# microXusb401_r15.net
KiCad netlist of a schematic drawn in EAGLE
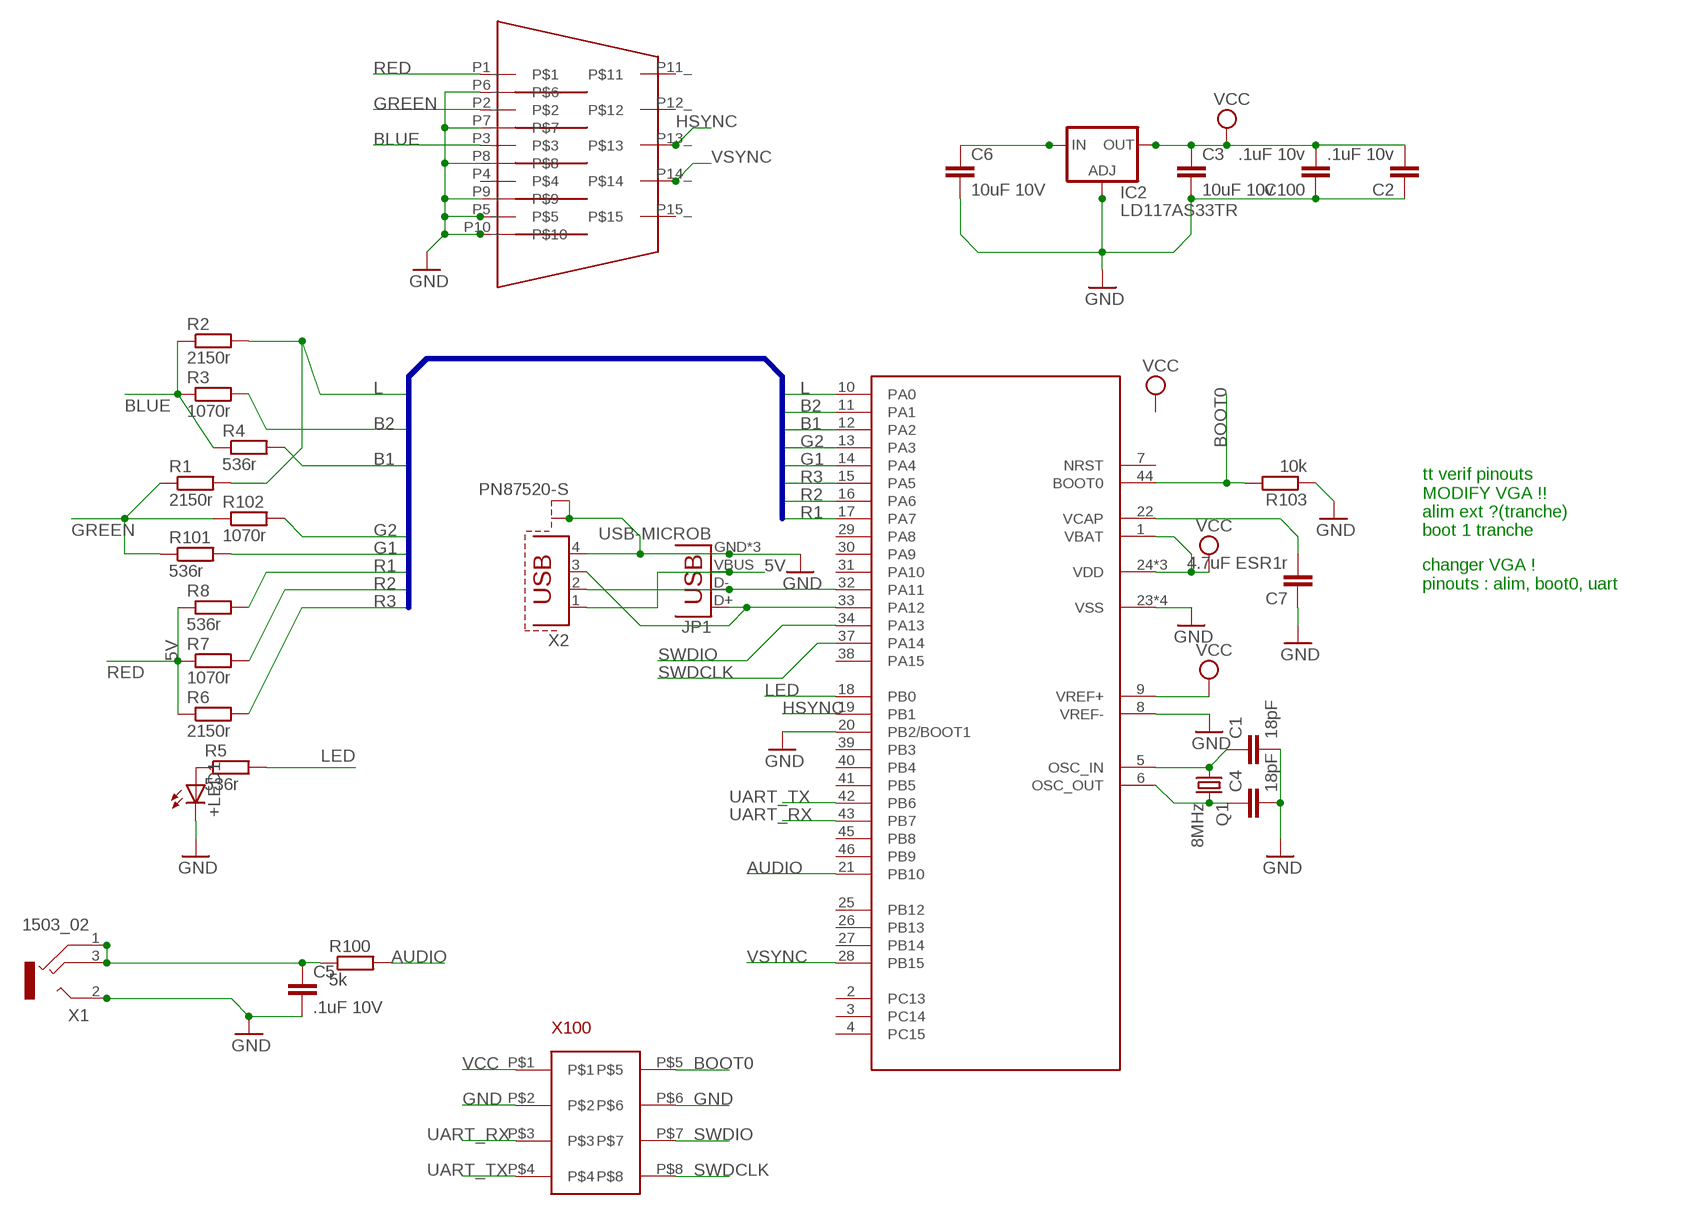
[diagram p0: schematic, sheet 1]

(export (version "E")
  (design (tool "Eeschema 10.0.6"))
  (components
    (comp (ref "+LED1")
      (value "LEDCHIPLED_0805")
      (footprint "eagle-import:CHIPLED_0805")
      (libsource (lib "eagle-import") (part "LEDCHIPLED_0805"))
    )
    (comp (ref "C1")
      (value "18pF")
      (footprint "eagle-import:C1608")
      (libsource (lib "eagle-import") (part "C-EUC1608"))
    )
    (comp (ref "C2")
      (value ".1uF 10v")
      (footprint "eagle-import:C1608")
      (libsource (lib "eagle-import") (part "C-EUC1608"))
    )
    (comp (ref "C3")
      (value "10uF 10v")
      (footprint "eagle-import:C1608")
      (libsource (lib "eagle-import") (part "C-EUC1608"))
    )
    (comp (ref "C4")
      (value "18pF")
      (footprint "eagle-import:C1608")
      (libsource (lib "eagle-import") (part "C-EUC1608"))
    )
    (comp (ref "C5")
      (value ".1uF 10V")
      (footprint "eagle-import:C1608")
      (libsource (lib "eagle-import") (part "C-EUC1608"))
    )
    (comp (ref "C6")
      (value "10uF 10V")
      (footprint "eagle-import:C1608")
      (libsource (lib "eagle-import") (part "C-EUC1608"))
    )
    (comp (ref "C7")
      (value "4.7uF ESR1r")
      (footprint "eagle-import:C1608")
      (libsource (lib "eagle-import") (part "C-EUC1608"))
    )
    (comp (ref "C100")
      (value ".1uF 10v")
      (footprint "eagle-import:C1608")
      (libsource (lib "eagle-import") (part "C-EUC1608"))
    )
    (comp (ref "CON1")
      (value "VGA_GTK_USLIM")
      (footprint "eagle-import:VGA_SLIM3")
      (libsource (lib "eagle-import") (part "VGA_GTK_USLIM"))
    )
    (comp (ref "IC1")
      (value "STM32F401CCUQFN48_B")
      (footprint "eagle-import:QFN-48")
      (libsource (lib "eagle-import") (part "STM32F401CCUQFN48_B"))
    )
    (comp (ref "IC2")
      (value "LD117AS33TR")
      (footprint "eagle-import:SOT223")
      (libsource (lib "eagle-import") (part "LD117A?S33TR"))
    )
    (comp (ref "JP1")
      (value "USB-MICROB")
      (footprint "eagle-import:USB-MICROB")
      (libsource (lib "eagle-import") (part "USB-MICROB"))
    )
    (comp (ref "Q1")
      (value "8MHz")
      (footprint "eagle-import:SM49")
      (libsource (lib "eagle-import") (part "CRYSTALSM49"))
    )
    (comp (ref "R1")
      (value "2150r")
      (footprint "eagle-import:R0603")
      (libsource (lib "eagle-import") (part "R-EU_R0603"))
    )
    (comp (ref "R2")
      (value "2150r")
      (footprint "eagle-import:R0603")
      (libsource (lib "eagle-import") (part "R-EU_R0603"))
    )
    (comp (ref "R3")
      (value "1070r")
      (footprint "eagle-import:R0603")
      (libsource (lib "eagle-import") (part "R-EU_R0603"))
    )
    (comp (ref "R4")
      (value "536r")
      (footprint "eagle-import:R0603")
      (libsource (lib "eagle-import") (part "R-EU_R0603"))
    )
    (comp (ref "R5")
      (value "536r")
      (footprint "eagle-import:R0603")
      (libsource (lib "eagle-import") (part "R-EU_R0603"))
    )
    (comp (ref "R6")
      (value "2150r")
      (footprint "eagle-import:R0603")
      (libsource (lib "eagle-import") (part "R-EU_R0603"))
    )
    (comp (ref "R7")
      (value "1070r")
      (footprint "eagle-import:R0603")
      (libsource (lib "eagle-import") (part "R-EU_R0603"))
    )
    (comp (ref "R8")
      (value "536r")
      (footprint "eagle-import:R0603")
      (libsource (lib "eagle-import") (part "R-EU_R0603"))
    )
    (comp (ref "R100")
      (value "5k")
      (footprint "eagle-import:R0603")
      (libsource (lib "eagle-import") (part "R-EU_R0603"))
    )
    (comp (ref "R101")
      (value "536r")
      (footprint "eagle-import:R0603")
      (libsource (lib "eagle-import") (part "R-EU_R0603"))
    )
    (comp (ref "R102")
      (value "1070r")
      (footprint "eagle-import:R0603")
      (libsource (lib "eagle-import") (part "R-EU_R0603"))
    )
    (comp (ref "R103")
      (value "10k")
      (footprint "eagle-import:R0603")
      (libsource (lib "eagle-import") (part "R-EU_R0603"))
    )
    (comp (ref "X1")
      (value "1503_02")
      (footprint "eagle-import:1503_02")
      (libsource (lib "eagle-import") (part "1503_02"))
    )
    (comp (ref "X2")
      (value "PN87520-S")
      (footprint "eagle-import:PN87520-S")
      (libsource (lib "eagle-import") (part "PN87520-S"))
    )
    (comp (ref "X100")
      (value "HEADER_BORDER_4X2")
      (footprint "eagle-import:HEADER_BORDER_4X2")
      (libsource (lib "eagle-import") (part "HEADER_BORDER_4X2"))
    )
  )
  (nets
    (net (code "1") (name "/5V") (class "Default")
      (node (ref "C6") (pin "1") (pinfunction "1_1") (pintype "passive"))
      (node (ref "IC2") (pin "3") (pinfunction "IN_3") (pintype "input"))
      (node (ref "JP1") (pin "VBUS") (pinfunction "VBUS_VBUS") (pintype "bidirectional"))
      (node (ref "X2") (pin "1") (pinfunction "1_1") (pintype "passive"))
    )
    (net (code "2") (name "/AUDIO") (class "Default")
      (node (ref "IC1") (pin "21") (pinfunction "PB10_21") (pintype "bidirectional"))
      (node (ref "R100") (pin "2") (pinfunction "2_2") (pintype "passive"))
    )
    (net (code "3") (name "/B1") (class "Default")
      (node (ref "IC1") (pin "12") (pinfunction "PA2_12") (pintype "bidirectional"))
      (node (ref "R4") (pin "2") (pinfunction "2_2") (pintype "passive"))
    )
    (net (code "4") (name "/B2") (class "Default")
      (node (ref "IC1") (pin "11") (pinfunction "PA1_11") (pintype "bidirectional"))
      (node (ref "R3") (pin "2") (pinfunction "2_2") (pintype "passive"))
    )
    (net (code "5") (name "/BLUE") (class "Default")
      (node (ref "CON1") (pin "P3_") (pinfunction "P$3_P3_") (pintype "bidirectional"))
      (node (ref "R2") (pin "1") (pinfunction "1_1") (pintype "passive"))
      (node (ref "R3") (pin "1") (pinfunction "1_1") (pintype "passive"))
      (node (ref "R4") (pin "1") (pinfunction "1_1") (pintype "passive"))
    )
    (net (code "6") (name "/BOOT0") (class "Default")
      (node (ref "IC1") (pin "44") (pinfunction "BOOT0_44") (pintype "bidirectional"))
      (node (ref "R103") (pin "2") (pinfunction "2_2") (pintype "passive"))
      (node (ref "X100") (pin "P$5") (pinfunction "P$5_P$5") (pintype "bidirectional"))
    )
    (net (code "7") (name "/G1") (class "Default")
      (node (ref "IC1") (pin "14") (pinfunction "PA4_14") (pintype "bidirectional"))
      (node (ref "R101") (pin "2") (pinfunction "2_2") (pintype "passive"))
    )
    (net (code "8") (name "/G2") (class "Default")
      (node (ref "IC1") (pin "13") (pinfunction "PA3_13") (pintype "bidirectional"))
      (node (ref "R102") (pin "2") (pinfunction "2_2") (pintype "passive"))
    )
    (net (code "9") (name "/GREEN") (class "Default")
      (node (ref "CON1") (pin "P2_") (pinfunction "P$2_P2_") (pintype "bidirectional"))
      (node (ref "R1") (pin "1") (pinfunction "1_1") (pintype "passive"))
      (node (ref "R101") (pin "1") (pinfunction "1_1") (pintype "passive"))
      (node (ref "R102") (pin "1") (pinfunction "1_1") (pintype "passive"))
    )
    (net (code "10") (name "/HSYNC") (class "Default")
      (node (ref "CON1") (pin "P13_") (pinfunction "P$13_P13_") (pintype "bidirectional"))
      (node (ref "IC1") (pin "19") (pinfunction "PB1_19") (pintype "bidirectional"))
    )
    (net (code "11") (name "/L") (class "Default")
      (node (ref "IC1") (pin "10") (pinfunction "PA0_10") (pintype "bidirectional"))
      (node (ref "R1") (pin "2") (pinfunction "2_2") (pintype "passive"))
      (node (ref "R2") (pin "2") (pinfunction "2_2") (pintype "passive"))
    )
    (net (code "12") (name "/LED") (class "Default")
      (node (ref "IC1") (pin "18") (pinfunction "PB0_18") (pintype "bidirectional"))
      (node (ref "R5") (pin "2") (pinfunction "2_2") (pintype "passive"))
    )
    (net (code "13") (name "/R1") (class "Default")
      (node (ref "IC1") (pin "17") (pinfunction "PA7_17") (pintype "bidirectional"))
      (node (ref "R8") (pin "2") (pinfunction "2_2") (pintype "passive"))
    )
    (net (code "14") (name "/R2") (class "Default")
      (node (ref "IC1") (pin "16") (pinfunction "PA6_16") (pintype "bidirectional"))
      (node (ref "R7") (pin "2") (pinfunction "2_2") (pintype "passive"))
    )
    (net (code "15") (name "/R3") (class "Default")
      (node (ref "IC1") (pin "15") (pinfunction "PA5_15") (pintype "bidirectional"))
      (node (ref "R6") (pin "2") (pinfunction "2_2") (pintype "passive"))
    )
    (net (code "16") (name "/RED") (class "Default")
      (node (ref "CON1") (pin "P1_") (pinfunction "P$1_P1_") (pintype "bidirectional"))
      (node (ref "R6") (pin "1") (pinfunction "1_1") (pintype "passive"))
      (node (ref "R7") (pin "1") (pinfunction "1_1") (pintype "passive"))
      (node (ref "R8") (pin "1") (pinfunction "1_1") (pintype "passive"))
    )
    (net (code "17") (name "/SWDCLK") (class "Default")
      (node (ref "IC1") (pin "37") (pinfunction "PA14_37") (pintype "bidirectional"))
      (node (ref "X100") (pin "P$8") (pinfunction "P$8_P$8") (pintype "bidirectional"))
    )
    (net (code "18") (name "/SWDIO") (class "Default")
      (node (ref "IC1") (pin "34") (pinfunction "PA13_34") (pintype "bidirectional"))
      (node (ref "X100") (pin "P$7") (pinfunction "P$7_P$7") (pintype "bidirectional"))
    )
    (net (code "19") (name "/UART_RX") (class "Default")
      (node (ref "IC1") (pin "43") (pinfunction "PB7_43") (pintype "bidirectional"))
      (node (ref "X100") (pin "P$3") (pinfunction "P$3_P$3") (pintype "bidirectional"))
    )
    (net (code "20") (name "/UART_TX") (class "Default")
      (node (ref "IC1") (pin "42") (pinfunction "PB6_42") (pintype "bidirectional"))
      (node (ref "X100") (pin "P$4") (pinfunction "P$4_P$4") (pintype "bidirectional"))
    )
    (net (code "21") (name "/VSYNC") (class "Default")
      (node (ref "CON1") (pin "P14_") (pinfunction "P$14_P14_") (pintype "bidirectional"))
      (node (ref "IC1") (pin "28") (pinfunction "PB15_28") (pintype "bidirectional"))
    )
    (net (code "22") (name "GND") (class "Default")
      (node (ref "+LED1") (pin "C") (pinfunction "C_C") (pintype "passive"))
      (node (ref "C1") (pin "2") (pinfunction "2_2") (pintype "passive"))
      (node (ref "C100") (pin "1") (pinfunction "1_1") (pintype "passive"))
      (node (ref "C2") (pin "1") (pinfunction "1_1") (pintype "passive"))
      (node (ref "C3") (pin "2") (pinfunction "2_2") (pintype "passive"))
      (node (ref "C4") (pin "2") (pinfunction "2_2") (pintype "passive"))
      (node (ref "C5") (pin "2") (pinfunction "2_2") (pintype "passive"))
      (node (ref "C6") (pin "2") (pinfunction "2_2") (pintype "passive"))
      (node (ref "C7") (pin "1") (pinfunction "1_1") (pintype "passive"))
      (node (ref "CON1") (pin "P10_") (pinfunction "P$10_P10_") (pintype "bidirectional"))
      (node (ref "CON1") (pin "P5_") (pinfunction "P$5_P5_") (pintype "bidirectional"))
      (node (ref "CON1") (pin "P6_") (pinfunction "P$6_P6_") (pintype "bidirectional"))
      (node (ref "CON1") (pin "P7_") (pinfunction "P$7_P7_") (pintype "bidirectional"))
      (node (ref "CON1") (pin "P8_") (pinfunction "P$8_P8_") (pintype "bidirectional"))
      (node (ref "CON1") (pin "P9_") (pinfunction "P$9_P9_") (pintype "bidirectional"))
      (node (ref "IC1") (pin "20") (pinfunction "PB2/BOOT1_20") (pintype "bidirectional"))
      (node (ref "IC1") (pin "23") (pinfunction "VSS_23") (pintype "bidirectional"))
      (node (ref "IC1") (pin "35") (pinfunction "VSS_35") (pintype "bidirectional"))
      (node (ref "IC1") (pin "47") (pinfunction "VSS_47") (pintype "bidirectional"))
      (node (ref "IC1") (pin "8") (pinfunction "VREF-_8") (pintype "bidirectional"))
      (node (ref "IC1") (pin "EXP") (pinfunction "VSS_EXP") (pintype "bidirectional"))
      (node (ref "IC2") (pin "1") (pinfunction "ADJ_1") (pintype "input"))
      (node (ref "JP1") (pin "GND") (pinfunction "GND_GND") (pintype "bidirectional"))
      (node (ref "JP1") (pin "MT1") (pinfunction "GND_MT1") (pintype "bidirectional"))
      (node (ref "JP1") (pin "MT2") (pinfunction "GND_MT2") (pintype "bidirectional"))
      (node (ref "R103") (pin "1") (pinfunction "1_1") (pintype "passive"))
      (node (ref "X1") (pin "2") (pinfunction "2_2") (pintype "passive"))
      (node (ref "X100") (pin "P$2") (pinfunction "P$2_P$2") (pintype "bidirectional"))
      (node (ref "X100") (pin "P$6") (pinfunction "P$6_P$6") (pintype "bidirectional"))
      (node (ref "X2") (pin "4") (pinfunction "4_4") (pintype "passive"))
      (node (ref "X2") (pin "S1") (pinfunction "S1_S1") (pintype "passive"))
      (node (ref "X2") (pin "S2") (pinfunction "S2_S2") (pintype "passive"))
    )
    (net (code "23") (name "Net-(+LED1-PadA)") (class "Default")
      (node (ref "+LED1") (pin "A") (pinfunction "A_A") (pintype "passive"))
      (node (ref "R5") (pin "1") (pinfunction "1_1") (pintype "passive"))
    )
    (net (code "24") (name "Net-(C5-Pad1)") (class "Default")
      (node (ref "C5") (pin "1") (pinfunction "1_1") (pintype "passive"))
      (node (ref "R100") (pin "1") (pinfunction "1_1") (pintype "passive"))
      (node (ref "X1") (pin "1") (pinfunction "1_1") (pintype "passive"))
      (node (ref "X1") (pin "3") (pinfunction "3_3") (pintype "passive"))
    )
    (net (code "25") (name "Net-(IC1-OSC_IN)") (class "Default")
      (node (ref "C1") (pin "1") (pinfunction "1_1") (pintype "passive"))
      (node (ref "IC1") (pin "5") (pinfunction "OSC_IN_5") (pintype "bidirectional"))
      (node (ref "Q1") (pin "1") (pinfunction "1_1") (pintype "passive"))
    )
    (net (code "26") (name "Net-(IC1-OSC_OUT)") (class "Default")
      (node (ref "C4") (pin "1") (pinfunction "1_1") (pintype "passive"))
      (node (ref "IC1") (pin "6") (pinfunction "OSC_OUT_6") (pintype "bidirectional"))
      (node (ref "Q1") (pin "2") (pinfunction "2_2") (pintype "passive"))
    )
    (net (code "27") (name "Net-(IC1-PA11)") (class "Default")
      (node (ref "IC1") (pin "32") (pinfunction "PA11_32") (pintype "bidirectional"))
      (node (ref "JP1") (pin "D-") (pinfunction "D-_D-") (pintype "bidirectional"))
      (node (ref "X2") (pin "2") (pinfunction "2_2") (pintype "passive"))
    )
    (net (code "28") (name "Net-(IC1-PA12)") (class "Default")
      (node (ref "IC1") (pin "33") (pinfunction "PA12_33") (pintype "bidirectional"))
      (node (ref "JP1") (pin "D+") (pinfunction "D+_D+") (pintype "bidirectional"))
      (node (ref "X2") (pin "3") (pinfunction "3_3") (pintype "passive"))
    )
    (net (code "29") (name "Net-(IC1-VCAP)") (class "Default")
      (node (ref "C7") (pin "2") (pinfunction "2_2") (pintype "passive"))
      (node (ref "IC1") (pin "22") (pinfunction "VCAP_22") (pintype "bidirectional"))
    )
    (net (code "30") (name "VCC") (class "Default")
      (node (ref "C100") (pin "2") (pinfunction "2_2") (pintype "passive"))
      (node (ref "C2") (pin "2") (pinfunction "2_2") (pintype "passive"))
      (node (ref "C3") (pin "1") (pinfunction "1_1") (pintype "passive"))
      (node (ref "IC1") (pin "1") (pinfunction "VBAT_1") (pintype "bidirectional"))
      (node (ref "IC1") (pin "24") (pinfunction "VDD_24") (pintype "bidirectional"))
      (node (ref "IC1") (pin "36") (pinfunction "VDD_36") (pintype "bidirectional"))
      (node (ref "IC1") (pin "48") (pinfunction "VDD_48") (pintype "bidirectional"))
      (node (ref "IC1") (pin "9") (pinfunction "VREF+_9") (pintype "bidirectional"))
      (node (ref "IC2") (pin "4") (pinfunction "OUT_4") (pintype "passive"))
      (node (ref "X100") (pin "P$1") (pinfunction "P$1_P$1") (pintype "bidirectional"))
    )
    (net (code "31") (name "unconnected-(CON1-P$4-PadP4_)") (class "Default")
      (node (ref "CON1") (pin "P4_") (pinfunction "P$4_P4_") (pintype "bidirectional"))
    )
    (net (code "32") (name "unconnected-(CON1-P$11-PadP11_)") (class "Default")
      (node (ref "CON1") (pin "P11_") (pinfunction "P$11_P11_") (pintype "bidirectional"))
    )
    (net (code "33") (name "unconnected-(CON1-P$12-PadP12_)") (class "Default")
      (node (ref "CON1") (pin "P12_") (pinfunction "P$12_P12_") (pintype "bidirectional"))
    )
    (net (code "34") (name "unconnected-(CON1-P$15-PadP15_)") (class "Default")
      (node (ref "CON1") (pin "P15_") (pinfunction "P$15_P15_") (pintype "bidirectional"))
    )
    (net (code "35") (name "unconnected-(IC1-NRST-Pad7)") (class "Default")
      (node (ref "IC1") (pin "7") (pinfunction "NRST_7") (pintype "bidirectional"))
    )
    (net (code "36") (name "unconnected-(IC1-PA8-Pad29)") (class "Default")
      (node (ref "IC1") (pin "29") (pinfunction "PA8_29") (pintype "bidirectional"))
    )
    (net (code "37") (name "unconnected-(IC1-PA9-Pad30)") (class "Default")
      (node (ref "IC1") (pin "30") (pinfunction "PA9_30") (pintype "bidirectional"))
    )
    (net (code "38") (name "unconnected-(IC1-PA10-Pad31)") (class "Default")
      (node (ref "IC1") (pin "31") (pinfunction "PA10_31") (pintype "bidirectional"))
    )
    (net (code "39") (name "unconnected-(IC1-PA15-Pad38)") (class "Default")
      (node (ref "IC1") (pin "38") (pinfunction "PA15_38") (pintype "bidirectional"))
    )
    (net (code "40") (name "unconnected-(IC1-PB3-Pad39)") (class "Default")
      (node (ref "IC1") (pin "39") (pinfunction "PB3_39") (pintype "bidirectional"))
    )
    (net (code "41") (name "unconnected-(IC1-PB4-Pad40)") (class "Default")
      (node (ref "IC1") (pin "40") (pinfunction "PB4_40") (pintype "bidirectional"))
    )
    (net (code "42") (name "unconnected-(IC1-PB5-Pad41)") (class "Default")
      (node (ref "IC1") (pin "41") (pinfunction "PB5_41") (pintype "bidirectional"))
    )
    (net (code "43") (name "unconnected-(IC1-PB8-Pad45)") (class "Default")
      (node (ref "IC1") (pin "45") (pinfunction "PB8_45") (pintype "bidirectional"))
    )
    (net (code "44") (name "unconnected-(IC1-PB9-Pad46)") (class "Default")
      (node (ref "IC1") (pin "46") (pinfunction "PB9_46") (pintype "bidirectional"))
    )
    (net (code "45") (name "unconnected-(IC1-PB12-Pad25)") (class "Default")
      (node (ref "IC1") (pin "25") (pinfunction "PB12_25") (pintype "bidirectional"))
    )
    (net (code "46") (name "unconnected-(IC1-PB13-Pad26)") (class "Default")
      (node (ref "IC1") (pin "26") (pinfunction "PB13_26") (pintype "bidirectional"))
    )
    (net (code "47") (name "unconnected-(IC1-PB14-Pad27)") (class "Default")
      (node (ref "IC1") (pin "27") (pinfunction "PB14_27") (pintype "bidirectional"))
    )
    (net (code "48") (name "unconnected-(IC1-PC13-Pad2)") (class "Default")
      (node (ref "IC1") (pin "2") (pinfunction "PC13_2") (pintype "bidirectional"))
    )
    (net (code "49") (name "unconnected-(IC1-PC14-Pad3)") (class "Default")
      (node (ref "IC1") (pin "3") (pinfunction "PC14_3") (pintype "bidirectional"))
    )
    (net (code "50") (name "unconnected-(IC1-PC15-Pad4)") (class "Default")
      (node (ref "IC1") (pin "4") (pinfunction "PC15_4") (pintype "bidirectional"))
    )
    (net (code "51") (name "unconnected-(X1-2-Pad2@2)") (class "Default")
      (node (ref "X1") (pin "2@2") (pinfunction "2_2@2") (pintype "passive"))
    )
  )
)
